# DS2482_1_Wire_Controller_copy.net
KiCad netlist of a schematic drawn in EAGLE
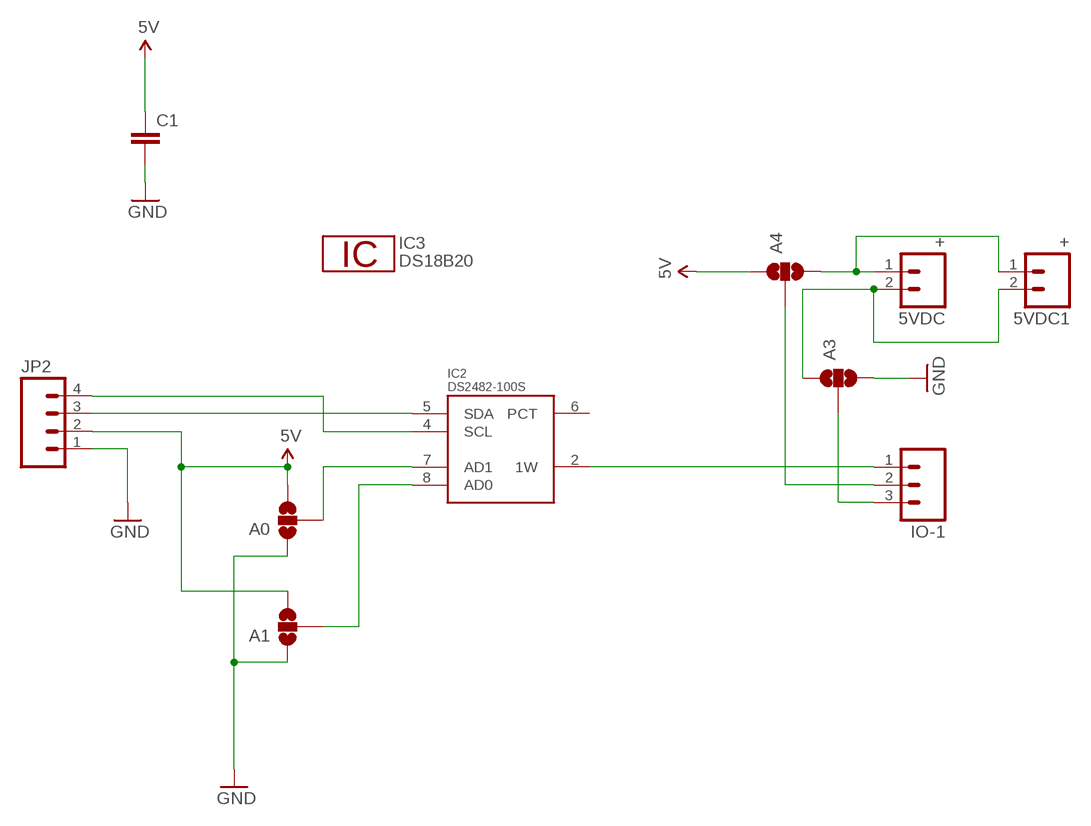
[diagram p0: schematic, sheet 1]

(export (version "E")
  (design (tool "Eeschema 10.0.6"))
  (components
    (comp (ref "5VDC")
      (value "+")
      (footprint "eagle-import:1X02")
      (libsource (lib "eagle-import") (part "M02PTH"))
    )
    (comp (ref "5VDC1")
      (value "+")
      (footprint "eagle-import:1X02")
      (libsource (lib "eagle-import") (part "M02PTH"))
    )
    (comp (ref "A0")
      (value "SOLDERJUMPER_2WAYS")
      (footprint "eagle-import:SJ_3")
      (libsource (lib "eagle-import") (part "SOLDERJUMPER_2WAYS"))
    )
    (comp (ref "A1")
      (value "SOLDERJUMPER_2WAYS")
      (footprint "eagle-import:SJ_3")
      (libsource (lib "eagle-import") (part "SOLDERJUMPER_2WAYS"))
    )
    (comp (ref "A3")
      (value "SOLDERJUMPER_2WAYS")
      (footprint "eagle-import:SJ_3")
      (libsource (lib "eagle-import") (part "SOLDERJUMPER_2WAYS"))
    )
    (comp (ref "A4")
      (value "SOLDERJUMPER_2WAYS")
      (footprint "eagle-import:SJ_3")
      (libsource (lib "eagle-import") (part "SOLDERJUMPER_2WAYS"))
    )
    (comp (ref "C1")
      (value "CAPPTH2")
      (footprint "eagle-import:CAP-PTH-SMALL2")
      (libsource (lib "eagle-import") (part "CAPPTH2"))
    )
    (comp (ref "IC2")
      (value "DS2482-100S")
      (footprint "eagle-import:SO08")
      (libsource (lib "eagle-import") (part "DS2482-100S"))
    )
    (comp (ref "IC3")
      (value "DS18B20")
      (footprint "eagle-import:TO92-")
      (libsource (lib "eagle-import") (part "DS18B20"))
    )
    (comp (ref "IO-1")
      (value "M03PTH")
      (footprint "eagle-import:1X03")
      (libsource (lib "eagle-import") (part "M03PTH"))
    )
    (comp (ref "JP2")
      (value "M04PTH")
      (footprint "eagle-import:1X04")
      (libsource (lib "eagle-import") (part "M04PTH"))
    )
  )
  (nets
    (net (code "1") (name "5V") (class "Default")
      (node (ref "A0") (pin "3") (pinfunction "3_3") (pintype "passive"))
      (node (ref "A1") (pin "3") (pinfunction "3_3") (pintype "passive"))
      (node (ref "A4") (pin "1") (pinfunction "1_1") (pintype "passive"))
      (node (ref "C1") (pin "1") (pinfunction "1_1") (pintype "passive"))
      (node (ref "JP2") (pin "2") (pinfunction "2_2") (pintype "passive"))
    )
    (net (code "2") (name "GND") (class "Default")
      (node (ref "A0") (pin "1") (pinfunction "1_1") (pintype "passive"))
      (node (ref "A1") (pin "1") (pinfunction "1_1") (pintype "passive"))
      (node (ref "A3") (pin "3") (pinfunction "3_3") (pintype "passive"))
      (node (ref "C1") (pin "2") (pinfunction "2_2") (pintype "passive"))
      (node (ref "JP2") (pin "1") (pinfunction "1_1") (pintype "passive"))
    )
    (net (code "3") (name "Net-(5VDC-Pad1)") (class "Default")
      (node (ref "5VDC") (pin "1") (pinfunction "1_1") (pintype "passive"))
      (node (ref "5VDC1") (pin "1") (pinfunction "1_1") (pintype "passive"))
      (node (ref "A4") (pin "3") (pinfunction "3_3") (pintype "passive"))
    )
    (net (code "4") (name "Net-(5VDC-Pad2)") (class "Default")
      (node (ref "5VDC") (pin "2") (pinfunction "2_2") (pintype "passive"))
      (node (ref "5VDC1") (pin "2") (pinfunction "2_2") (pintype "passive"))
      (node (ref "A3") (pin "1") (pinfunction "1_1") (pintype "passive"))
    )
    (net (code "5") (name "Net-(A3-Pad2)") (class "Default")
      (node (ref "A3") (pin "2") (pinfunction "2_2") (pintype "passive"))
      (node (ref "IO-1") (pin "3") (pinfunction "3_3") (pintype "passive"))
    )
    (net (code "6") (name "Net-(A4-Pad2)") (class "Default")
      (node (ref "A4") (pin "2") (pinfunction "2_2") (pintype "passive"))
      (node (ref "IO-1") (pin "2") (pinfunction "2_2") (pintype "passive"))
    )
    (net (code "7") (name "Net-(IC2A-1W)") (class "Default")
      (node (ref "IC2") (pin "2") (pinfunction "1W_2") (pintype "open_collector"))
      (node (ref "IO-1") (pin "1") (pinfunction "1_1") (pintype "passive"))
    )
    (net (code "8") (name "Net-(IC2A-AD0)") (class "Default")
      (node (ref "A1") (pin "2") (pinfunction "2_2") (pintype "passive"))
      (node (ref "IC2") (pin "8") (pinfunction "AD0_8") (pintype "input"))
    )
    (net (code "9") (name "Net-(IC2A-AD1)") (class "Default")
      (node (ref "A0") (pin "2") (pinfunction "2_2") (pintype "passive"))
      (node (ref "IC2") (pin "7") (pinfunction "AD1_7") (pintype "input"))
    )
    (net (code "10") (name "Net-(IC2A-SCL)") (class "Default")
      (node (ref "IC2") (pin "4") (pinfunction "SCL_4") (pintype "input"))
      (node (ref "JP2") (pin "4") (pinfunction "4_4") (pintype "passive"))
    )
    (net (code "11") (name "Net-(IC2A-SDA)") (class "Default")
      (node (ref "IC2") (pin "5") (pinfunction "SDA_5") (pintype "bidirectional"))
      (node (ref "JP2") (pin "3") (pinfunction "3_3") (pintype "passive"))
    )
    (net (code "12") (name "unconnected-(IC2A-PCT-Pad6)") (class "Default")
      (node (ref "IC2") (pin "6") (pinfunction "PCT_6") (pintype "output"))
    )
  )
)
